# p05_leds.net
KiCad netlist of a schematic drawn in Altium Designer
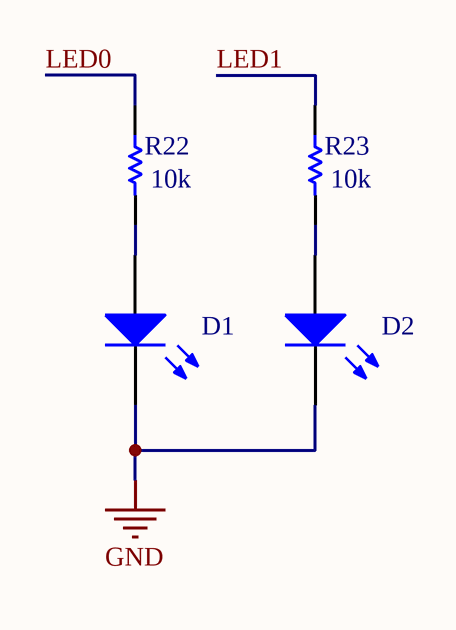
[diagram p0: p05_leds.SchDoc]

(export (version "E")
  (design (tool "Eeschema 10.0.6"))
  (components
    (comp (ref "D1")
      (value "LED0")
      (description "Typical INFRARED GaAs LED")
      (fields (field (name "PUBLISHER") "Altium Limited"))
      (libsource (lib "Miscellaneous Devices") (part "LED0"))
    )
    (comp (ref "D2")
      (value "LED0")
      (description "Typical INFRARED GaAs LED")
      (fields (field (name "PUBLISHER") "Altium Limited"))
      (libsource (lib "Miscellaneous Devices") (part "LED0"))
    )
    (comp (ref "R22")
      (value "10k")
      (footprint "6-0805_M")
      (description "Resistor")
      (fields (field (name "Comment") "Res1") (field (name "PUBLISHER") "Altium Limited"))
      (libsource (lib "Miscellaneous Devices") (part "Res1"))
    )
    (comp (ref "R23")
      (value "10k")
      (footprint "6-0805_M")
      (description "Resistor")
      (fields (field (name "Comment") "Res1") (field (name "PUBLISHER") "Altium Limited"))
      (libsource (lib "Miscellaneous Devices") (part "Res1"))
    )
  )
  (nets
    (net (code "1") (name "/LED0") (class "Default")
      (node (ref "R22") (pin "1") (pinfunction "1_1") (pintype "passive"))
    )
    (net (code "2") (name "/LED1") (class "Default")
      (node (ref "R23") (pin "1") (pinfunction "1_1") (pintype "passive"))
    )
    (net (code "3") (name "GND") (class "Default")
      (node (ref "D1") (pin "2") (pinfunction "K_2") (pintype "passive"))
      (node (ref "D2") (pin "2") (pinfunction "K_2") (pintype "passive"))
    )
    (net (code "4") (name "Net-(D1-A)") (class "Default")
      (node (ref "D1") (pin "1") (pinfunction "A_1") (pintype "passive"))
      (node (ref "R22") (pin "2") (pinfunction "2_2") (pintype "passive"))
    )
    (net (code "5") (name "Net-(D2-A)") (class "Default")
      (node (ref "D2") (pin "1") (pinfunction "A_1") (pintype "passive"))
      (node (ref "R23") (pin "2") (pinfunction "2_2") (pintype "passive"))
    )
  )
)
